# CPU.net
KiCad netlist of a schematic drawn in Altium Designer
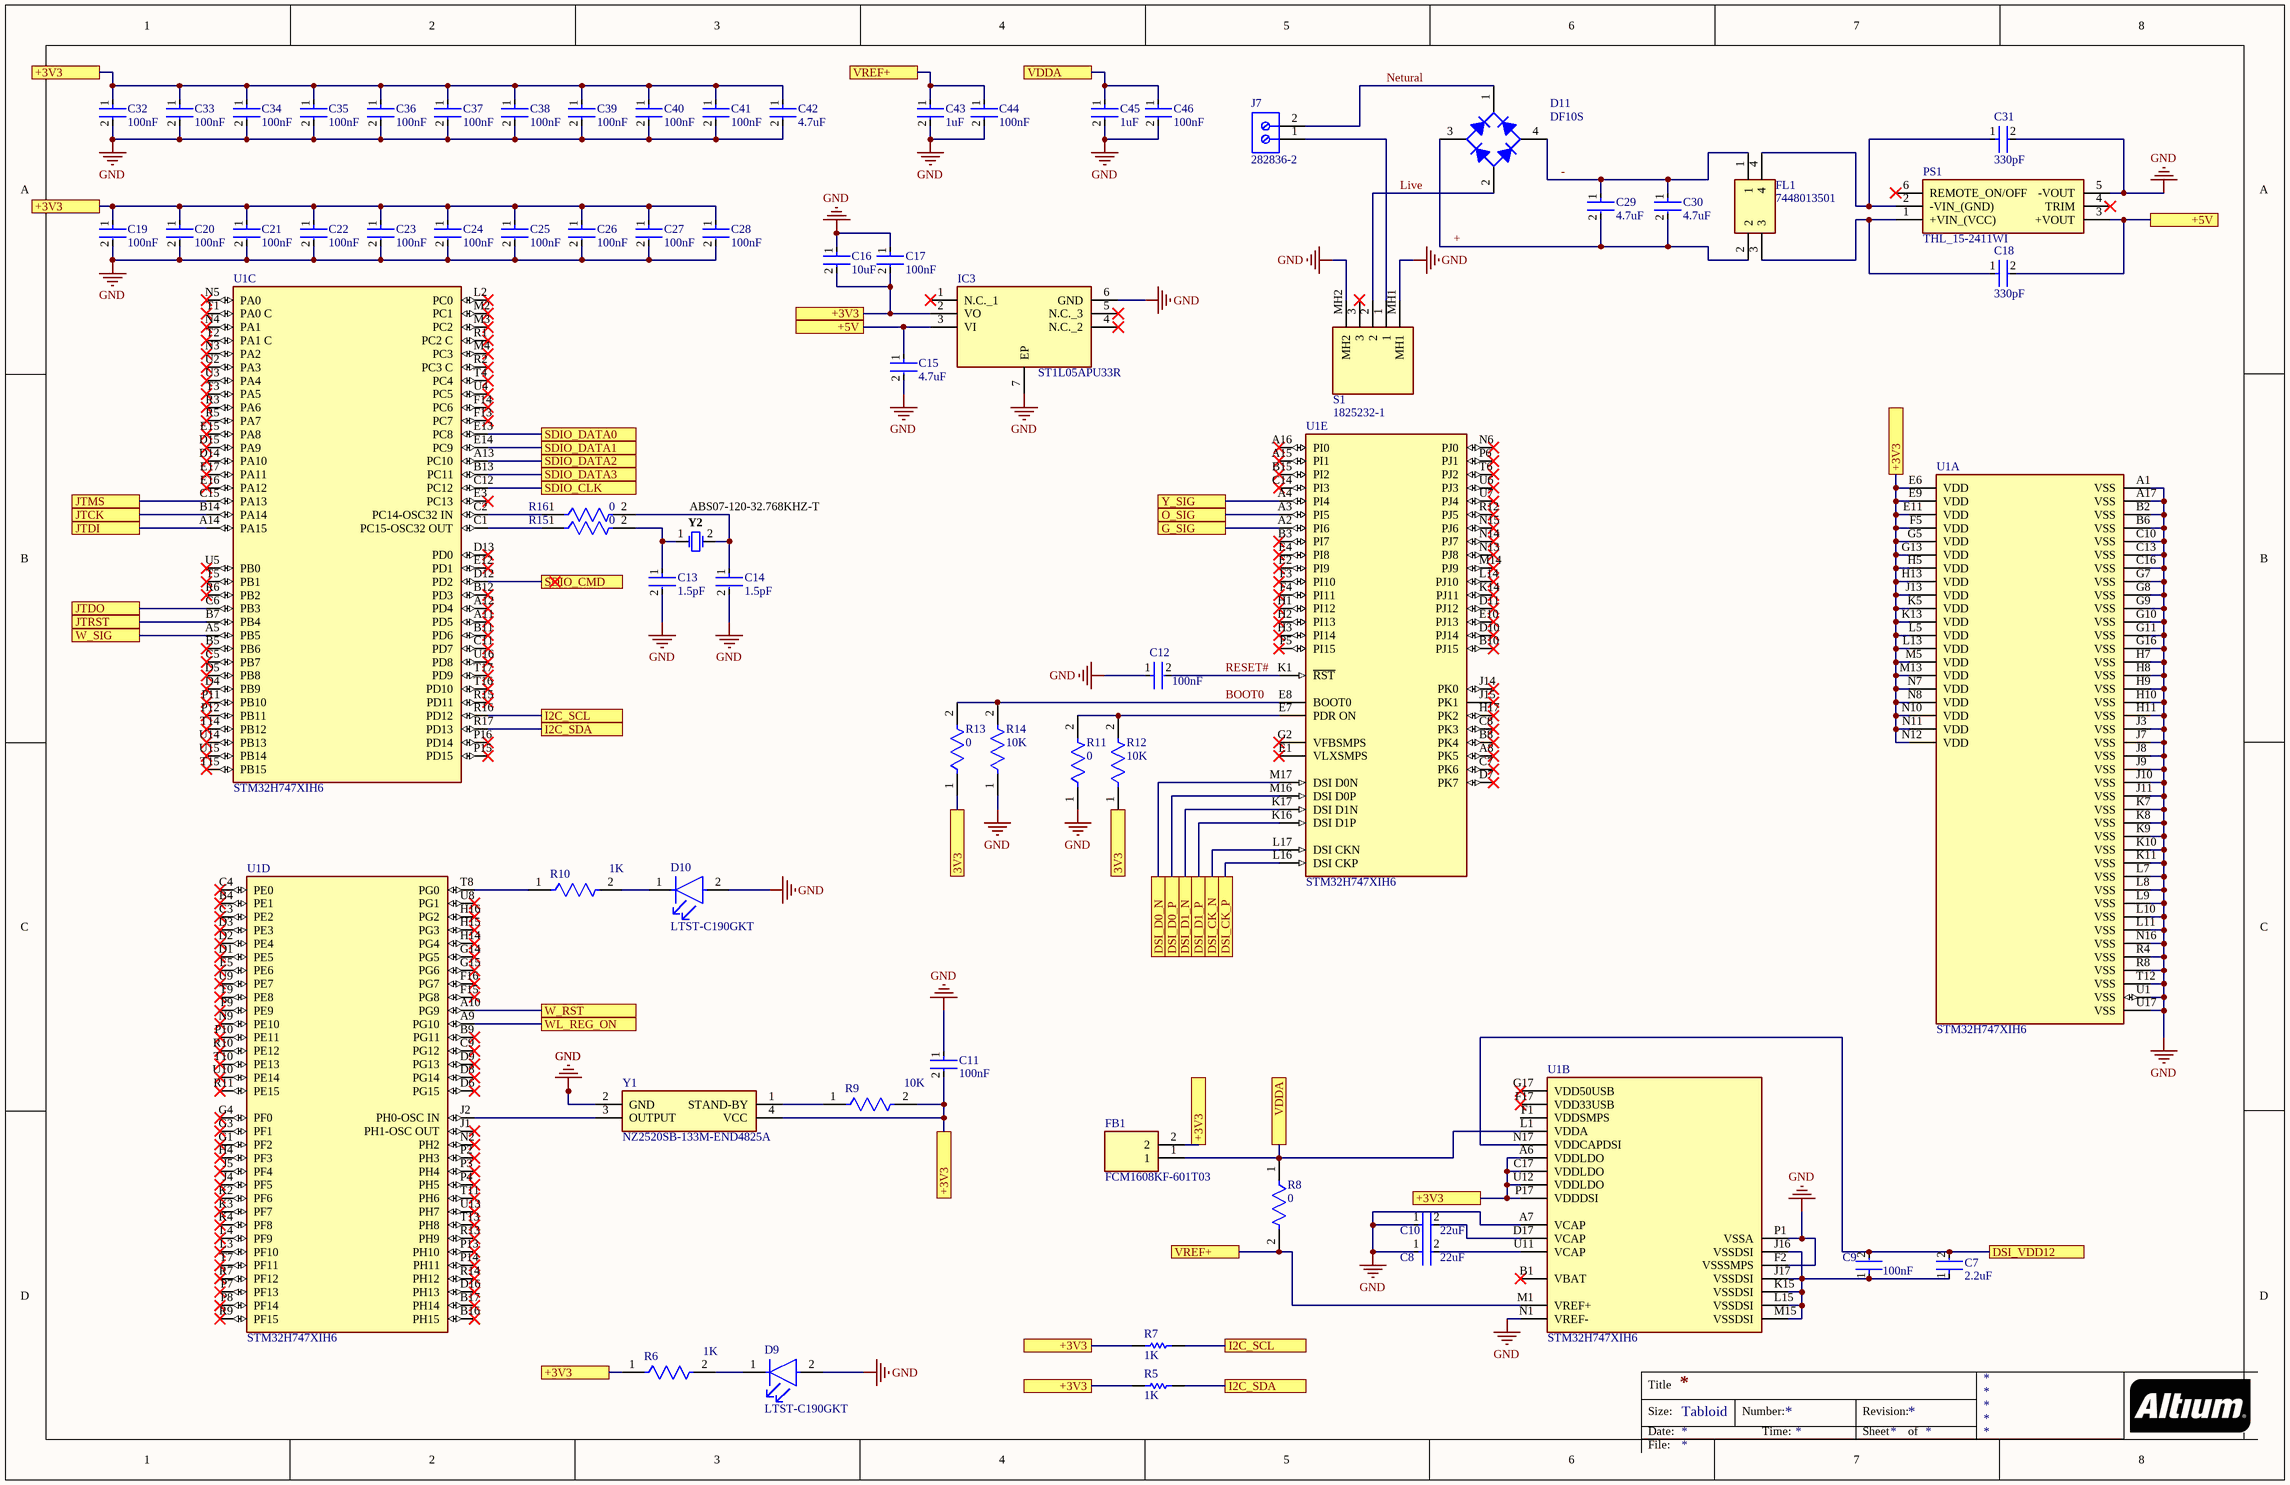
[diagram p0: CPU.SchDoc]

(export (version "E")
  (design (tool "Eeschema 10.0.6"))
  (components
    (comp (ref "C7")
      (value "2.2uF")
      (footprint "FP-GJM155-0_05-IPC_C")
      (description "Multi-Layer Ceramic Capacitor 1.5pF C0G  ±0.1pF 0402 Paper T/R")
      (fields (field (name "VOLTAGE") "50V"))
      (libsource (lib "Altium Content Vault") (part "02cd4be3c70576c341d710602a673aa"))
    )
    (comp (ref "C8")
      (value "22uF")
      (footprint "FP-GJM155-0_05-IPC_C")
      (description "Multi-Layer Ceramic Capacitor 1.5pF C0G  ±0.1pF 0402 Paper T/R")
      (fields (field (name "VOLTAGE") "50V"))
      (libsource (lib "Altium Content Vault") (part "02cd4be3c70576c341d710602a673aa"))
    )
    (comp (ref "C9")
      (value "100nF")
      (footprint "FP-GJM155-0_05-IPC_C")
      (description "Multi-Layer Ceramic Capacitor 1.5pF C0G  ±0.1pF 0402 Paper T/R")
      (fields (field (name "VOLTAGE") "50V"))
      (libsource (lib "Altium Content Vault") (part "02cd4be3c70576c341d710602a673aa"))
    )
    (comp (ref "C10")
      (value "22uF")
      (footprint "FP-GJM155-0_05-IPC_C")
      (description "Multi-Layer Ceramic Capacitor 1.5pF C0G  ±0.1pF 0402 Paper T/R")
      (fields (field (name "VOLTAGE") "50V"))
      (libsource (lib "Altium Content Vault") (part "02cd4be3c70576c341d710602a673aa"))
    )
    (comp (ref "C11")
      (value "100nF")
      (footprint "FP-GJM155-0_05-IPC_C")
      (description "Multi-Layer Ceramic Capacitor 1.5pF C0G  ±0.1pF 0402 Paper T/R")
      (fields (field (name "VOLTAGE") "50V"))
      (libsource (lib "Altium Content Vault") (part "02cd4be3c70576c341d710602a673aa"))
    )
    (comp (ref "C12")
      (value "100nF")
      (footprint "FP-GJM155-0_05-IPC_C")
      (description "Multi-Layer Ceramic Capacitor 1.5pF C0G  ±0.1pF 0402 Paper T/R")
      (fields (field (name "VOLTAGE") "50V"))
      (libsource (lib "Altium Content Vault") (part "02cd4be3c70576c341d710602a673aa"))
    )
    (comp (ref "C13")
      (value "1.5pF")
      (footprint "FP-GJM155-0_05-IPC_C")
      (description "Multi-Layer Ceramic Capacitor 1.5pF C0G  ±0.1pF 0402 Paper T/R")
      (fields (field (name "VOLTAGE") "50V"))
      (libsource (lib "Altium Content Vault") (part "02cd4be3c70576c341d710602a673aa"))
    )
    (comp (ref "C14")
      (value "1.5pF")
      (footprint "FP-GJM155-0_05-IPC_C")
      (description "Multi-Layer Ceramic Capacitor 1.5pF C0G  ±0.1pF 0402 Paper T/R")
      (fields (field (name "VOLTAGE") "50V"))
      (libsource (lib "Altium Content Vault") (part "02cd4be3c70576c341d710602a673aa"))
    )
    (comp (ref "C15")
      (value "4.7uF")
      (footprint "FP-GRM155-0_1-IPC_B")
      (description "Chip Multilayer Ceramic Capacitors for General Purpose, 0402, 4.7uF, X5R, 15%, 20%, 6.3V")
      (fields (field (name "VOLTAGE") "6.3V") (field (name "TOLERANCE") "20%"))
      (libsource (lib "Altium Content Vault") (part "11868f565c42a9108669ba33697ecf6"))
    )
    (comp (ref "C16")
      (value "10uF")
      (footprint "FP-GRM188-0_1-e0_2_0_55-IPC_A")
      (description "Chip Multilayer Ceramic Capacitors for General Purpose, 0603, 10uF, X5R, 15%, 20%, 6.3V")
      (fields (field (name "VOLTAGE") "6.3V") (field (name "TOLERANCE") "20%"))
      (libsource (lib "Altium Content Vault") (part "02cd4be3c70576c341d710602a673aa"))
    )
    (comp (ref "C17")
      (value "100nF")
      (footprint "FP-GRM033-0_03-MFG")
      (description "Chip Multilayer Ceramic Capacitors for General Purpose, 0201, 0.10uF, X5R, 15%, 10%, 6.3V")
      (fields (field (name "VOLTAGE") "6.3V") (field (name "TOLERANCE") "10%"))
      (libsource (lib "Altium Content Vault") (part "b4654b650e69147ec39a6b967a45e02"))
    )
    (comp (ref "C18")
      (value "330pF")
      (footprint "FP-GRM155-0_05-MFG")
      (description "Chip Multilayer Ceramic Capacitors for General Purpose, 0402, 330pF, C0G, 30ppm/°C, 5%, 50V")
      (fields (field (name "TOLERANCE") "5%") (field (name "VOLTAGE") "50V"))
      (libsource (lib "Altium Content Vault") (part "02cd4be3c70576c341d710602a673aa"))
    )
    (comp (ref "C19")
      (value "100nF")
      (footprint "FP-GRM033-0_03-MFG")
      (description "Chip Multilayer Ceramic Capacitors for General Purpose, 0201, 0.10uF, X5R, 15%, 10%, 6.3V")
      (fields (field (name "VOLTAGE") "6.3V") (field (name "TOLERANCE") "10%"))
      (libsource (lib "Altium Content Vault") (part "b4654b650e69147ec39a6b967a45e02"))
    )
    (comp (ref "C20")
      (value "100nF")
      (footprint "FP-GRM033-0_03-MFG")
      (description "Chip Multilayer Ceramic Capacitors for General Purpose, 0201, 0.10uF, X5R, 15%, 10%, 6.3V")
      (fields (field (name "VOLTAGE") "6.3V") (field (name "TOLERANCE") "10%"))
      (libsource (lib "Altium Content Vault") (part "b4654b650e69147ec39a6b967a45e02"))
    )
    (comp (ref "C21")
      (value "100nF")
      (footprint "FP-GRM033-0_03-MFG")
      (description "Chip Multilayer Ceramic Capacitors for General Purpose, 0201, 0.10uF, X5R, 15%, 10%, 6.3V")
      (fields (field (name "VOLTAGE") "6.3V") (field (name "TOLERANCE") "10%"))
      (libsource (lib "Altium Content Vault") (part "b4654b650e69147ec39a6b967a45e02"))
    )
    (comp (ref "C22")
      (value "100nF")
      (footprint "FP-GRM033-0_03-MFG")
      (description "Chip Multilayer Ceramic Capacitors for General Purpose, 0201, 0.10uF, X5R, 15%, 10%, 6.3V")
      (fields (field (name "VOLTAGE") "6.3V") (field (name "TOLERANCE") "10%"))
      (libsource (lib "Altium Content Vault") (part "b4654b650e69147ec39a6b967a45e02"))
    )
    (comp (ref "C23")
      (value "100nF")
      (footprint "FP-GRM033-0_03-MFG")
      (description "Chip Multilayer Ceramic Capacitors for General Purpose, 0201, 0.10uF, X5R, 15%, 10%, 6.3V")
      (fields (field (name "VOLTAGE") "6.3V") (field (name "TOLERANCE") "10%"))
      (libsource (lib "Altium Content Vault") (part "b4654b650e69147ec39a6b967a45e02"))
    )
    (comp (ref "C24")
      (value "100nF")
      (footprint "FP-GRM033-0_03-MFG")
      (description "Chip Multilayer Ceramic Capacitors for General Purpose, 0201, 0.10uF, X5R, 15%, 10%, 6.3V")
      (fields (field (name "VOLTAGE") "6.3V") (field (name "TOLERANCE") "10%"))
      (libsource (lib "Altium Content Vault") (part "b4654b650e69147ec39a6b967a45e02"))
    )
    (comp (ref "C25")
      (value "100nF")
      (footprint "FP-GRM033-0_03-MFG")
      (description "Chip Multilayer Ceramic Capacitors for General Purpose, 0201, 0.10uF, X5R, 15%, 10%, 6.3V")
      (fields (field (name "VOLTAGE") "6.3V") (field (name "TOLERANCE") "10%"))
      (libsource (lib "Altium Content Vault") (part "b4654b650e69147ec39a6b967a45e02"))
    )
    (comp (ref "C26")
      (value "100nF")
      (footprint "FP-GRM033-0_03-MFG")
      (description "Chip Multilayer Ceramic Capacitors for General Purpose, 0201, 0.10uF, X5R, 15%, 10%, 6.3V")
      (fields (field (name "VOLTAGE") "6.3V") (field (name "TOLERANCE") "10%"))
      (libsource (lib "Altium Content Vault") (part "b4654b650e69147ec39a6b967a45e02"))
    )
    (comp (ref "C27")
      (value "100nF")
      (footprint "FP-GRM033-0_03-MFG")
      (description "Chip Multilayer Ceramic Capacitors for General Purpose, 0201, 0.10uF, X5R, 15%, 10%, 6.3V")
      (fields (field (name "VOLTAGE") "6.3V") (field (name "TOLERANCE") "10%"))
      (libsource (lib "Altium Content Vault") (part "b4654b650e69147ec39a6b967a45e02"))
    )
    (comp (ref "C28")
      (value "100nF")
      (footprint "FP-GRM033-0_03-MFG")
      (description "Chip Multilayer Ceramic Capacitors for General Purpose, 0201, 0.10uF, X5R, 15%, 10%, 6.3V")
      (fields (field (name "VOLTAGE") "6.3V") (field (name "TOLERANCE") "10%"))
      (libsource (lib "Altium Content Vault") (part "b4654b650e69147ec39a6b967a45e02"))
    )
    (comp (ref "C29")
      (value "4.7uF")
      (footprint "FP-GRM155-0_1-IPC_B")
      (description "Chip Multilayer Ceramic Capacitors for General Purpose, 0402, 4.7uF, X5R, 15%, 20%, 6.3V")
      (fields (field (name "VOLTAGE") "6.3V") (field (name "TOLERANCE") "20%"))
      (libsource (lib "Altium Content Vault") (part "11868f565c42a9108669ba33697ecf6"))
    )
    (comp (ref "C30")
      (value "4.7uF")
      (footprint "FP-GRM155-0_1-IPC_B")
      (description "Chip Multilayer Ceramic Capacitors for General Purpose, 0402, 4.7uF, X5R, 15%, 20%, 6.3V")
      (fields (field (name "VOLTAGE") "6.3V") (field (name "TOLERANCE") "20%"))
      (libsource (lib "Altium Content Vault") (part "11868f565c42a9108669ba33697ecf6"))
    )
    (comp (ref "C31")
      (value "330pF")
      (footprint "FP-GRM155-0_05-MFG")
      (description "Chip Multilayer Ceramic Capacitors for General Purpose, 0402, 330pF, C0G, 30ppm/°C, 5%, 50V")
      (fields (field (name "TOLERANCE") "5%") (field (name "VOLTAGE") "50V"))
      (libsource (lib "Altium Content Vault") (part "02cd4be3c70576c341d710602a673aa"))
    )
    (comp (ref "C32")
      (value "100nF")
      (footprint "FP-GRM033-0_03-MFG")
      (description "Chip Multilayer Ceramic Capacitors for General Purpose, 0201, 0.10uF, X5R, 15%, 10%, 6.3V")
      (fields (field (name "VOLTAGE") "6.3V") (field (name "TOLERANCE") "10%"))
      (libsource (lib "Altium Content Vault") (part "b4654b650e69147ec39a6b967a45e02"))
    )
    (comp (ref "C33")
      (value "100nF")
      (footprint "FP-GRM033-0_03-MFG")
      (description "Chip Multilayer Ceramic Capacitors for General Purpose, 0201, 0.10uF, X5R, 15%, 10%, 6.3V")
      (fields (field (name "VOLTAGE") "6.3V") (field (name "TOLERANCE") "10%"))
      (libsource (lib "Altium Content Vault") (part "b4654b650e69147ec39a6b967a45e02"))
    )
    (comp (ref "C34")
      (value "100nF")
      (footprint "FP-GRM033-0_03-MFG")
      (description "Chip Multilayer Ceramic Capacitors for General Purpose, 0201, 0.10uF, X5R, 15%, 10%, 6.3V")
      (fields (field (name "VOLTAGE") "6.3V") (field (name "TOLERANCE") "10%"))
      (libsource (lib "Altium Content Vault") (part "b4654b650e69147ec39a6b967a45e02"))
    )
    (comp (ref "C35")
      (value "100nF")
      (footprint "FP-GRM033-0_03-MFG")
      (description "Chip Multilayer Ceramic Capacitors for General Purpose, 0201, 0.10uF, X5R, 15%, 10%, 6.3V")
      (fields (field (name "VOLTAGE") "6.3V") (field (name "TOLERANCE") "10%"))
      (libsource (lib "Altium Content Vault") (part "b4654b650e69147ec39a6b967a45e02"))
    )
    (comp (ref "C36")
      (value "100nF")
      (footprint "FP-GRM033-0_03-MFG")
      (description "Chip Multilayer Ceramic Capacitors for General Purpose, 0201, 0.10uF, X5R, 15%, 10%, 6.3V")
      (fields (field (name "VOLTAGE") "6.3V") (field (name "TOLERANCE") "10%"))
      (libsource (lib "Altium Content Vault") (part "b4654b650e69147ec39a6b967a45e02"))
    )
    (comp (ref "C37")
      (value "100nF")
      (footprint "FP-GRM033-0_03-MFG")
      (description "Chip Multilayer Ceramic Capacitors for General Purpose, 0201, 0.10uF, X5R, 15%, 10%, 6.3V")
      (fields (field (name "VOLTAGE") "6.3V") (field (name "TOLERANCE") "10%"))
      (libsource (lib "Altium Content Vault") (part "b4654b650e69147ec39a6b967a45e02"))
    )
    (comp (ref "C38")
      (value "100nF")
      (footprint "FP-GRM033-0_03-MFG")
      (description "Chip Multilayer Ceramic Capacitors for General Purpose, 0201, 0.10uF, X5R, 15%, 10%, 6.3V")
      (fields (field (name "VOLTAGE") "6.3V") (field (name "TOLERANCE") "10%"))
      (libsource (lib "Altium Content Vault") (part "b4654b650e69147ec39a6b967a45e02"))
    )
    (comp (ref "C39")
      (value "100nF")
      (footprint "FP-GRM033-0_03-MFG")
      (description "Chip Multilayer Ceramic Capacitors for General Purpose, 0201, 0.10uF, X5R, 15%, 10%, 6.3V")
      (fields (field (name "VOLTAGE") "6.3V") (field (name "TOLERANCE") "10%"))
      (libsource (lib "Altium Content Vault") (part "b4654b650e69147ec39a6b967a45e02"))
    )
    (comp (ref "C40")
      (value "100nF")
      (footprint "FP-GRM033-0_03-MFG")
      (description "Chip Multilayer Ceramic Capacitors for General Purpose, 0201, 0.10uF, X5R, 15%, 10%, 6.3V")
      (fields (field (name "VOLTAGE") "6.3V") (field (name "TOLERANCE") "10%"))
      (libsource (lib "Altium Content Vault") (part "b4654b650e69147ec39a6b967a45e02"))
    )
    (comp (ref "C41")
      (value "100nF")
      (footprint "FP-GRM033-0_03-MFG")
      (description "Chip Multilayer Ceramic Capacitors for General Purpose, 0201, 0.10uF, X5R, 15%, 10%, 6.3V")
      (fields (field (name "VOLTAGE") "6.3V") (field (name "TOLERANCE") "10%"))
      (libsource (lib "Altium Content Vault") (part "b4654b650e69147ec39a6b967a45e02"))
    )
    (comp (ref "C42")
      (value "4.7uF")
      (footprint "FP-GRM155-0_1-IPC_B")
      (description "Chip Multilayer Ceramic Capacitors for General Purpose, 0402, 4.7uF, X5R, 15%, 20%, 6.3V")
      (fields (field (name "VOLTAGE") "6.3V") (field (name "TOLERANCE") "20%"))
      (libsource (lib "Altium Content Vault") (part "11868f565c42a9108669ba33697ecf6"))
    )
    (comp (ref "C43")
      (value "1uF")
      (footprint "FP-GRM15-0_1-MFG")
      (description "CAP CER 1UF 10V X5R 0402")
      (fields
        (field (name "OCTOPART") "https://octopart.com/grm155r61a105ke15d-murata-197442")
        (field (name "MANUFACTURER PART NUMBER") "GRM155R61A105KE15D")
      )
      (libsource (lib "Altium Content Vault") (part "02cd4be3c70576c341d710602a673aa"))
    )
    (comp (ref "C44")
      (value "100nF")
      (footprint "FP-GRM033-0_03-MFG")
      (description "Chip Multilayer Ceramic Capacitors for General Purpose, 0201, 0.10uF, X5R, 15%, 10%, 6.3V")
      (fields (field (name "VOLTAGE") "6.3V") (field (name "TOLERANCE") "10%"))
      (libsource (lib "Altium Content Vault") (part "b4654b650e69147ec39a6b967a45e02"))
    )
    (comp (ref "C45")
      (value "1uF")
      (footprint "FP-GRM15-0_1-MFG")
      (description "CAP CER 1UF 10V X5R 0402")
      (fields
        (field (name "OCTOPART") "https://octopart.com/grm155r61a105ke15d-murata-197442")
        (field (name "MANUFACTURER PART NUMBER") "GRM155R61A105KE15D")
      )
      (libsource (lib "Altium Content Vault") (part "02cd4be3c70576c341d710602a673aa"))
    )
    (comp (ref "C46")
      (value "100nF")
      (footprint "FP-GRM033-0_03-MFG")
      (description "Chip Multilayer Ceramic Capacitors for General Purpose, 0201, 0.10uF, X5R, 15%, 10%, 6.3V")
      (fields (field (name "VOLTAGE") "6.3V") (field (name "TOLERANCE") "10%"))
      (libsource (lib "Altium Content Vault") (part "b4654b650e69147ec39a6b967a45e02"))
    )
    (comp (ref "D9")
      (value "LTST-C190GKT")
      (footprint "FP-LTST-C190GKT-MFG")
      (description "LED GREEN CLEAR CHIP SMD")
      (fields (field (name "VOLTAGE") "2V"))
      (libsource (lib "Altium Content Vault") (part "8706943c75ba83719d021d2fdc84c58"))
    )
    (comp (ref "D10")
      (value "LTST-C190GKT")
      (footprint "FP-LTST-C190GKT-MFG")
      (description "LED GREEN CLEAR CHIP SMD")
      (fields (field (name "VOLTAGE") "2V"))
      (libsource (lib "Altium Content Vault") (part "8706943c75ba83719d021d2fdc84c58"))
    )
    (comp (ref "D11")
      (value "DF10S")
      (footprint "FAIR-SDIP-4_V")
      (description "Bridge Rectifier, 1.5 A, 1000 V, 4-Pin SDIP, RoHS, Tape and Reel")
      (fields (field (name "MANUFACTURER") "FairchildSemiconductor"))
      (libsource (lib "Altium Content Vault") (part "D-KACC-4"))
    )
    (comp (ref "FB1")
      (value "FCM1608KF-601T03")
      (footprint "SamacSys:BEADC1608X95N")
      (description "Ferrite Bead")
      (libsource (lib "*") (part "FCM1608KF-601T03"))
    )
    (comp (ref "FL1")
      (value "7448013501")
      (footprint "SamacSys:7448013501")
      (description "Filter")
      (fields (field (name "MOUSER PART NUMBER") "710-7448013501"))
      (libsource (lib "*") (part "7448013501"))
    )
    (comp (ref "IC3")
      (value "ST1L05APU33R")
      (footprint "SamacSys:SON95P300X300X100-7N-D")
      (description "Integrated Circuit")
      (fields (field (name "MOUSER PART NUMBER") "511-ST1L05APU33R"))
      (libsource (lib "*") (part "ST1L05APU33R"))
    )
    (comp (ref "J7")
      (value "282836-2")
      (footprint "TECO-282836-2_V")
      (description "Female Header, Pitch 5 mm, 1 x 2 Position, Height 10 mm, Tail Length 3.5 mm, Rohs, Bulk")
      (fields (field (name "VOLTAGE") "300V") (field (name "MANUFACTURER") "TE Connectivity"))
      (libsource (lib "Altium Content Vault") (part "CN-1P-F-TB2"))
    )
    (comp (ref "PS1")
      (value "THL_15-2411WI")
      (footprint "SamacSys:THL152411WI")
      (description "Power Supply")
      (fields
        (field (name "MANUFACTURER_PART_NUMBER") "THL 15-2411WI")
        (field (name "MOUSER PART NUMBER") "495-THL15-2411WI")
      )
      (libsource (lib "*") (part "THL_15-2411WI"))
    )
    (comp (ref "R5")
      (value "1K")
      (footprint "RESC1608X55X30LL20T20")
      (fields (field (name "MANUFACTURER") "Panasonic") (field (name "PART NUMBER") "ERA3AEB102V"))
      (libsource (lib "Altium Content Vault") (part "RES"))
    )
    (comp (ref "R6")
      (value "1K")
      (footprint "FP-CRCW0402-e3-MFG")
      (description "RES Thick Film, 1kΩ, 1%, 0.063W, 100ppm/°C, 0402")
      (fields (field (name "TOLERANCE") "1%"))
      (libsource (lib "Altium Content Vault") (part "1029c3af85768c4190bb7ad29bc67b5"))
    )
    (comp (ref "R7")
      (value "1K")
      (footprint "RESC1608X55X30LL20T20")
      (fields (field (name "MANUFACTURER") "Panasonic") (field (name "PART NUMBER") "ERA3AEB102V"))
      (libsource (lib "Altium Content Vault") (part "RES"))
    )
    (comp (ref "R8")
      (value "0")
      (footprint "FP-CRCW0402-e3-IPC_C")
      (description "RES Thick Film, 0Ω, 0.063W, 0402")
      (fields (field (name "TOLERANCE") "5%"))
      (libsource (lib "Altium Content Vault") (part "1029c3af85768c4190bb7ad29bc67b5"))
    )
    (comp (ref "R9")
      (value "10K")
      (footprint "FP-CRCW0402-e3-MFG")
      (description "RES Thick Film, 1kΩ, 1%, 0.063W, 100ppm/°C, 0402")
      (fields (field (name "TOLERANCE") "1%"))
      (libsource (lib "Altium Content Vault") (part "1029c3af85768c4190bb7ad29bc67b5"))
    )
    (comp (ref "R10")
      (value "1K")
      (footprint "FP-CRCW0402-e3-MFG")
      (description "RES Thick Film, 1kΩ, 1%, 0.063W, 100ppm/°C, 0402")
      (fields (field (name "TOLERANCE") "1%"))
      (libsource (lib "Altium Content Vault") (part "1029c3af85768c4190bb7ad29bc67b5"))
    )
    (comp (ref "R11")
      (value "0")
      (footprint "FP-CRCW0402-e3-IPC_C")
      (description "RES Thick Film, 0Ω, 0.063W, 0402")
      (fields (field (name "TOLERANCE") "5%"))
      (libsource (lib "Altium Content Vault") (part "1029c3af85768c4190bb7ad29bc67b5"))
    )
    (comp (ref "R12")
      (value "10K")
      (footprint "FP-CRCW0402-e3-IPC_C")
      (description "RES Thick Film, 0Ω, 0.063W, 0402")
      (fields (field (name "TOLERANCE") "5%"))
      (libsource (lib "Altium Content Vault") (part "1029c3af85768c4190bb7ad29bc67b5"))
    )
    (comp (ref "R13")
      (value "0")
      (footprint "FP-CRCW0402-e3-IPC_C")
      (description "RES Thick Film, 0Ω, 0.063W, 0402")
      (fields (field (name "TOLERANCE") "5%"))
      (libsource (lib "Altium Content Vault") (part "1029c3af85768c4190bb7ad29bc67b5"))
    )
    (comp (ref "R14")
      (value "10K")
      (footprint "FP-CRCW0402-e3-IPC_C")
      (description "RES Thick Film, 0Ω, 0.063W, 0402")
      (fields (field (name "TOLERANCE") "5%"))
      (libsource (lib "Altium Content Vault") (part "1029c3af85768c4190bb7ad29bc67b5"))
    )
    (comp (ref "R15")
      (value "0")
      (footprint "FP-CRCW0402-e3-IPC_C")
      (description "RES Thick Film, 0Ω, 0.063W, 0402")
      (fields (field (name "TOLERANCE") "5%"))
      (libsource (lib "Altium Content Vault") (part "1029c3af85768c4190bb7ad29bc67b5"))
    )
    (comp (ref "R16")
      (value "0")
      (footprint "FP-CRCW0402-e3-IPC_C")
      (description "RES Thick Film, 0Ω, 0.063W, 0402")
      (fields (field (name "TOLERANCE") "5%"))
      (libsource (lib "Altium Content Vault") (part "1029c3af85768c4190bb7ad29bc67b5"))
    )
    (comp (ref "S1")
      (value "1825232-1")
      (footprint "SamacSys:18252321")
      (description "Switch")
      (fields (field (name "MOUSER PART NUMBER") "655-1825232-1"))
      (libsource (lib "*") (part "1825232-1"))
    )
    (comp (ref "U1")
      (value "STM32H747XIH6")
      (footprint "FP-TFBGA240+25-A07U-MFG")
      (description "HIGH-PERFORMANCE AND DSP WITH DP")
      (fields
        (field (name "MANUFACTURER") "STMicroelectronics")
        (field (name "OCTOPART") "https://octopart.com/stm32h747xih6-stmicroelectronics-100293943")
      )
      (libsource (lib "Altium Content Vault") (part "41f839bdfd00d9510c8672f0f410bfb"))
    )
    (comp (ref "Y1")
      (value "NZ2520SB-133M-END4825A")
      (footprint "SamacSys:NZ2520SD")
      (description "Crystal or Oscillator")
      (fields (field (name "MOUSER PART NUMBER") "344-NZ2520SB1334825A"))
      (libsource (lib "*") (part "NZ2520SB-133M-END4825A"))
    )
    (comp (ref "Y2")
      (value "ABS07-120-32.768KHZ-T")
      (footprint "ABRA-ABS07_A_V")
      (description "Tuning Fork Crystal, 32.768 KHz, +/- 20 ppm, -40 to 85 degC, 2-Pin SMD, RoHS, Tape and Reel")
      (fields (field (name "MANUFACTURER") "Abracon") (field (name "TOLERANCE") "20ppm"))
      (libsource (lib "Altium Content Vault") (part "XTAL-1-2-2"))
    )
  )
  (nets
    (net (code "1") (name "/+") (class "Default")
      (node (ref "C29") (pin "2") (pinfunction "2_2") (pintype "passive"))
      (node (ref "C30") (pin "2") (pinfunction "2_2") (pintype "passive"))
      (node (ref "D11") (pin "3") (pinfunction "C_3") (pintype "passive"))
      (node (ref "FL1") (pin "2") (pinfunction "2_2") (pintype "passive"))
    )
    (net (code "2") (name "/+3V3") (class "Default")
      (node (ref "C11") (pin "2") (pinfunction "2_2") (pintype "passive"))
      (node (ref "C16") (pin "2") (pinfunction "2_2") (pintype "passive"))
      (node (ref "C17") (pin "2") (pinfunction "2_2") (pintype "passive"))
      (node (ref "C19") (pin "1") (pinfunction "1_1") (pintype "passive"))
      (node (ref "C20") (pin "1") (pinfunction "1_1") (pintype "passive"))
      (node (ref "C21") (pin "1") (pinfunction "1_1") (pintype "passive"))
      (node (ref "C22") (pin "1") (pinfunction "1_1") (pintype "passive"))
      (node (ref "C23") (pin "1") (pinfunction "1_1") (pintype "passive"))
      (node (ref "C24") (pin "1") (pinfunction "1_1") (pintype "passive"))
      (node (ref "C25") (pin "1") (pinfunction "1_1") (pintype "passive"))
      (node (ref "C26") (pin "1") (pinfunction "1_1") (pintype "passive"))
      (node (ref "C27") (pin "1") (pinfunction "1_1") (pintype "passive"))
      (node (ref "C28") (pin "1") (pinfunction "1_1") (pintype "passive"))
      (node (ref "C32") (pin "1") (pinfunction "1_1") (pintype "passive"))
      (node (ref "C33") (pin "1") (pinfunction "1_1") (pintype "passive"))
      (node (ref "C34") (pin "1") (pinfunction "1_1") (pintype "passive"))
      (node (ref "C35") (pin "1") (pinfunction "1_1") (pintype "passive"))
      (node (ref "C36") (pin "1") (pinfunction "1_1") (pintype "passive"))
      (node (ref "C37") (pin "1") (pinfunction "1_1") (pintype "passive"))
      (node (ref "C38") (pin "1") (pinfunction "1_1") (pintype "passive"))
      (node (ref "C39") (pin "1") (pinfunction "1_1") (pintype "passive"))
      (node (ref "C40") (pin "1") (pinfunction "1_1") (pintype "passive"))
      (node (ref "C41") (pin "1") (pinfunction "1_1") (pintype "passive"))
      (node (ref "C42") (pin "1") (pinfunction "1_1") (pintype "passive"))
      (node (ref "FB1") (pin "2") (pinfunction "2_2") (pintype "passive"))
      (node (ref "IC3") (pin "2") (pinfunction "VO_2") (pintype "passive"))
      (node (ref "R5") (pin "1") (pinfunction "1_1") (pintype "passive"))
      (node (ref "R6") (pin "1") (pinfunction "1_1") (pintype "passive"))
      (node (ref "R7") (pin "1") (pinfunction "1_1") (pintype "passive"))
      (node (ref "R9") (pin "2") (pinfunction "2_2") (pintype "passive"))
      (node (ref "U1") (pin "A6") (pinfunction "VDDLDO_A6") (pintype "power_in"))
      (node (ref "U1") (pin "C17") (pinfunction "VDDLDO_C17") (pintype "power_in"))
      (node (ref "U1") (pin "E11") (pinfunction "VDD_E11") (pintype "power_in"))
      (node (ref "U1") (pin "E6") (pinfunction "VDD_E6") (pintype "power_in"))
      (node (ref "U1") (pin "E9") (pinfunction "VDD_E9") (pintype "power_in"))
      (node (ref "U1") (pin "F5") (pinfunction "VDD_F5") (pintype "power_in"))
      (node (ref "U1") (pin "G13") (pinfunction "VDD_G13") (pintype "power_in"))
      (node (ref "U1") (pin "G5") (pinfunction "VDD_G5") (pintype "power_in"))
      (node (ref "U1") (pin "H13") (pinfunction "VDD_H13") (pintype "power_in"))
      (node (ref "U1") (pin "H5") (pinfunction "VDD_H5") (pintype "power_in"))
      (node (ref "U1") (pin "J13") (pinfunction "VDD_J13") (pintype "power_in"))
      (node (ref "U1") (pin "K13") (pinfunction "VDD_K13") (pintype "power_in"))
      (node (ref "U1") (pin "K5") (pinfunction "VDD_K5") (pintype "power_in"))
      (node (ref "U1") (pin "L13") (pinfunction "VDD_L13") (pintype "power_in"))
      (node (ref "U1") (pin "L5") (pinfunction "VDD_L5") (pintype "power_in"))
      (node (ref "U1") (pin "M13") (pinfunction "VDD_M13") (pintype "power_in"))
      (node (ref "U1") (pin "M5") (pinfunction "VDD_M5") (pintype "power_in"))
      (node (ref "U1") (pin "N10") (pinfunction "VDD_N10") (pintype "power_in"))
      (node (ref "U1") (pin "N11") (pinfunction "VDD_N11") (pintype "power_in"))
      (node (ref "U1") (pin "N12") (pinfunction "VDD_N12") (pintype "power_in"))
      (node (ref "U1") (pin "N7") (pinfunction "VDD_N7") (pintype "power_in"))
      (node (ref "U1") (pin "N8") (pinfunction "VDD_N8") (pintype "power_in"))
      (node (ref "U1") (pin "P17") (pinfunction "VDDDSI_P17") (pintype "power_in"))
      (node (ref "U1") (pin "U12") (pinfunction "VDDLDO_U12") (pintype "power_in"))
      (node (ref "Y1") (pin "4") (pinfunction "VCC_4") (pintype "passive"))
    )
    (net (code "3") (name "/+5V") (class "Default")
      (node (ref "C15") (pin "1") (pinfunction "1_1") (pintype "passive"))
      (node (ref "C18") (pin "2") (pinfunction "2_2") (pintype "passive"))
      (node (ref "IC3") (pin "3") (pinfunction "VI_3") (pintype "passive"))
      (node (ref "PS1") (pin "3") (pinfunction "+VOUT_3") (pintype "passive"))
    )
    (net (code "4") (name "/-") (class "Default")
      (node (ref "C29") (pin "1") (pinfunction "1_1") (pintype "passive"))
      (node (ref "C30") (pin "1") (pinfunction "1_1") (pintype "passive"))
      (node (ref "D11") (pin "4") (pinfunction "C_4") (pintype "passive"))
      (node (ref "FL1") (pin "1") (pinfunction "1_1") (pintype "passive"))
    )
    (net (code "5") (name "/3V3") (class "Default")
      (node (ref "R12") (pin "1") (pinfunction "1_1") (pintype "passive"))
      (node (ref "R13") (pin "1") (pinfunction "1_1") (pintype "passive"))
    )
    (net (code "6") (name "/BOOT0") (class "Default")
      (node (ref "R13") (pin "2") (pinfunction "2_2") (pintype "passive"))
      (node (ref "R14") (pin "2") (pinfunction "2_2") (pintype "passive"))
      (node (ref "U1") (pin "E8") (pinfunction "BOOT0_E8") (pintype "passive"))
    )
    (net (code "7") (name "/DSI_CK_N") (class "Default")
      (node (ref "U1") (pin "L17") (pinfunction "DSI_CKN_L17") (pintype "input"))
    )
    (net (code "8") (name "/DSI_CK_P") (class "Default")
      (node (ref "U1") (pin "L16") (pinfunction "DSI_CKP_L16") (pintype "input"))
    )
    (net (code "9") (name "/DSI_D0_N") (class "Default")
      (node (ref "U1") (pin "M17") (pinfunction "DSI_D0N_M17") (pintype "input"))
    )
    (net (code "10") (name "/DSI_D0_P") (class "Default")
      (node (ref "U1") (pin "M16") (pinfunction "DSI_D0P_M16") (pintype "input"))
    )
    (net (code "11") (name "/DSI_D1_N") (class "Default")
      (node (ref "U1") (pin "K17") (pinfunction "DSI_D1N_K17") (pintype "input"))
    )
    (net (code "12") (name "/DSI_D1_P") (class "Default")
      (node (ref "U1") (pin "K16") (pinfunction "DSI_D1P_K16") (pintype "input"))
    )
    (net (code "13") (name "/DSI_VDD12") (class "Default")
      (node (ref "C7") (pin "2") (pinfunction "2_2") (pintype "passive"))
      (node (ref "C9") (pin "2") (pinfunction "2_2") (pintype "passive"))
      (node (ref "U1") (pin "N17") (pinfunction "VDDCAPDSI_N17") (pintype "power_in"))
    )
    (net (code "14") (name "/G_SIG") (class "Default")
      (node (ref "U1") (pin "A2") (pinfunction "PI6_A2") (pintype "bidirectional"))
    )
    (net (code "15") (name "/I2C_SCL") (class "Default")
      (node (ref "R7") (pin "2") (pinfunction "2_2") (pintype "passive"))
      (node (ref "U1") (pin "R16") (pinfunction "PD12_R16") (pintype "bidirectional"))
    )
    (net (code "16") (name "/I2C_SDA") (class "Default")
      (node (ref "R5") (pin "2") (pinfunction "2_2") (pintype "passive"))
      (node (ref "U1") (pin "R17") (pinfunction "PD13_R17") (pintype "bidirectional"))
    )
    (net (code "17") (name "/JTCK") (class "Default")
      (node (ref "U1") (pin "B14") (pinfunction "PA14_B14") (pintype "bidirectional"))
    )
    (net (code "18") (name "/JTDI") (class "Default")
      (node (ref "U1") (pin "A14") (pinfunction "PA15_A14") (pintype "bidirectional"))
    )
    (net (code "19") (name "/JTDO") (class "Default")
      (node (ref "U1") (pin "C6") (pinfunction "PB3_C6") (pintype "bidirectional"))
    )
    (net (code "20") (name "/JTMS") (class "Default")
      (node (ref "U1") (pin "C15") (pinfunction "PA13_C15") (pintype "bidirectional"))
    )
    (net (code "21") (name "/JTRST") (class "Default")
      (node (ref "U1") (pin "B7") (pinfunction "PB4_B7") (pintype "bidirectional"))
    )
    (net (code "22") (name "/Live") (class "Default")
      (node (ref "D11") (pin "2") (pinfunction "A_2") (pintype "passive"))
      (node (ref "S1") (pin "2") (pinfunction "2_2") (pintype "passive"))
    )
    (net (code "23") (name "/Netural") (class "Default")
      (node (ref "D11") (pin "1") (pinfunction "K_1") (pintype "passive"))
      (node (ref "J7") (pin "2") (pinfunction "2_2") (pintype "passive"))
    )
    (net (code "24") (name "/O_SIG") (class "Default")
      (node (ref "U1") (pin "A3") (pinfunction "PI5_A3") (pintype "bidirectional"))
    )
    (net (code "25") (name "/RESET#") (class "Default")
      (node (ref "C12") (pin "2") (pinfunction "2_2") (pintype "passive"))
      (node (ref "U1") (pin "K1") (pinfunction "~{RST}_K1") (pintype "input"))
    )
    (net (code "26") (name "/SDIO_CLK") (class "Default")
      (node (ref "U1") (pin "C12") (pinfunction "PC12_C12") (pintype "bidirectional"))
    )
    (net (code "27") (name "/SDIO_CMD") (class "Default")
      (node (ref "U1") (pin "D12") (pinfunction "PD2_D12") (pintype "bidirectional"))
    )
    (net (code "28") (name "/SDIO_DATA0") (class "Default")
      (node (ref "U1") (pin "E13") (pinfunction "PC8_E13") (pintype "bidirectional"))
    )
    (net (code "29") (name "/SDIO_DATA1") (class "Default")
      (node (ref "U1") (pin "E14") (pinfunction "PC9_E14") (pintype "bidirectional"))
    )
    (net (code "30") (name "/SDIO_DATA2") (class "Default")
      (node (ref "U1") (pin "A13") (pinfunction "PC10_A13") (pintype "bidirectional"))
    )
    (net (code "31") (name "/SDIO_DATA3") (class "Default")
      (node (ref "U1") (pin "B13") (pinfunction "PC11_B13") (pintype "bidirectional"))
    )
    (net (code "32") (name "/VDDA") (class "Default")
      (node (ref "C45") (pin "1") (pinfunction "1_1") (pintype "passive"))
      (node (ref "C46") (pin "1") (pinfunction "1_1") (pintype "passive"))
      (node (ref "FB1") (pin "1") (pinfunction "1_1") (pintype "passive"))
      (node (ref "R8") (pin "1") (pinfunction "1_1") (pintype "passive"))
      (node (ref "U1") (pin "L1") (pinfunction "VDDA_L1") (pintype "power_in"))
    )
    (net (code "33") (name "/VREF+") (class "Default")
      (node (ref "C43") (pin "1") (pinfunction "1_1") (pintype "passive"))
      (node (ref "C44") (pin "1") (pinfunction "1_1") (pintype "passive"))
      (node (ref "R8") (pin "2") (pinfunction "2_2") (pintype "passive"))
      (node (ref "U1") (pin "M1") (pinfunction "VREF+_M1") (pintype "power_in"))
    )
    (net (code "34") (name "/WL_REG_ON") (class "Default")
      (node (ref "U1") (pin "A9") (pinfunction "PG10_A9") (pintype "bidirectional"))
    )
    (net (code "35") (name "/W_RST") (class "Default")
      (node (ref "U1") (pin "A10") (pinfunction "PG9_A10") (pintype "bidirectional"))
    )
    (net (code "36") (name "/W_SIG") (class "Default")
      (node (ref "U1") (pin "A5") (pinfunction "PB5_A5") (pintype "bidirectional"))
    )
    (net (code "37") (name "/Y_SIG") (class "Default")
      (node (ref "U1") (pin "A4") (pinfunction "PI4_A4") (pintype "bidirectional"))
    )
    (net (code "38") (name "GND") (class "Default")
      (node (ref "C10") (pin "1") (pinfunction "1_1") (pintype "passive"))
      (node (ref "C11") (pin "1") (pinfunction "1_1") (pintype "passive"))
      (node (ref "C12") (pin "1") (pinfunction "1_1") (pintype "passive"))
      (node (ref "C13") (pin "2") (pinfunction "2_2") (pintype "passive"))
      (node (ref "C14") (pin "2") (pinfunction "2_2") (pintype "passive"))
      (node (ref "C15") (pin "2") (pinfunction "2_2") (pintype "passive"))
      (node (ref "C16") (pin "1") (pinfunction "1_1") (pintype "passive"))
      (node (ref "C17") (pin "1") (pinfunction "1_1") (pintype "passive"))
      (node (ref "C19") (pin "2") (pinfunction "2_2") (pintype "passive"))
      (node (ref "C20") (pin "2") (pinfunction "2_2") (pintype "passive"))
      (node (ref "C21") (pin "2") (pinfunction "2_2") (pintype "passive"))
      (node (ref "C22") (pin "2") (pinfunction "2_2") (pintype "passive"))
      (node (ref "C23") (pin "2") (pinfunction "2_2") (pintype "passive"))
      (node (ref "C24") (pin "2") (pinfunction "2_2") (pintype "passive"))
      (node (ref "C25") (pin "2") (pinfunction "2_2") (pintype "passive"))
      (node (ref "C26") (pin "2") (pinfunction "2_2") (pintype "passive"))
      (node (ref "C27") (pin "2") (pinfunction "2_2") (pintype "passive"))
      (node (ref "C28") (pin "2") (pinfunction "2_2") (pintype "passive"))
      (node (ref "C31") (pin "2") (pinfunction "2_2") (pintype "passive"))
      (node (ref "C32") (pin "2") (pinfunction "2_2") (pintype "passive"))
      (node (ref "C33") (pin "2") (pinfunction "2_2") (pintype "passive"))
      (node (ref "C34") (pin "2") (pinfunction "2_2") (pintype "passive"))
      (node (ref "C35") (pin "2") (pinfunction "2_2") (pintype "passive"))
      (node (ref "C36") (pin "2") (pinfunction "2_2") (pintype "passive"))
      (node (ref "C37") (pin "2") (pinfunction "2_2") (pintype "passive"))
      (node (ref "C38") (pin "2") (pinfunction "2_2") (pintype "passive"))
      (node (ref "C39") (pin "2") (pinfunction "2_2") (pintype "passive"))
      (node (ref "C40") (pin "2") (pinfunction "2_2") (pintype "passive"))
      (node (ref "C41") (pin "2") (pinfunction "2_2") (pintype "passive"))
      (node (ref "C42") (pin "2") (pinfunction "2_2") (pintype "passive"))
      (node (ref "C43") (pin "2") (pinfunction "2_2") (pintype "passive"))
      (node (ref "C44") (pin "2") (pinfunction "2_2") (pintype "passive"))
      (node (ref "C45") (pin "2") (pinfunction "2_2") (pintype "passive"))
      (node (ref "C46") (pin "2") (pinfunction "2_2") (pintype "passive"))
      (node (ref "C8") (pin "1") (pinfunction "1_1") (pintype "passive"))
      (node (ref "D10") (pin "2") (pinfunction "A_2") (pintype "passive"))
      (node (ref "D9") (pin "2") (pinfunction "A_2") (pintype "passive"))
      (node (ref "IC3") (pin "6") (pinfunction "GND_6") (pintype "passive"))
      (node (ref "IC3") (pin "7") (pinfunction "EP_7") (pintype "passive"))
      (node (ref "PS1") (pin "5") (pinfunction "-VOUT_5") (pintype "passive"))
      (node (ref "R11") (pin "1") (pinfunction "1_1") (pintype "passive"))
      (node (ref "R14") (pin "1") (pinfunction "1_1") (pintype "passive"))
      (node (ref "S1") (pin "MH1") (pinfunction "MH1_MH1") (pintype "passive"))
      (node (ref "S1") (pin "MH2") (pinfunction "MH2_MH2") (pintype "passive"))
      (node (ref "U1") (pin "A1") (pinfunction "VSS_A1") (pintype "power_in"))
      (node (ref "U1") (pin "A17") (pinfunction "VSS_A17") (pintype "power_in"))
      (node (ref "U1") (pin "A7") (pinfunction "VCAP_A7") (pintype "power_in"))
      (node (ref "U1") (pin "B2") (pinfunction "VSS_B2") (pintype "power_in"))
      (node (ref "U1") (pin "B6") (pinfunction "VSS_B6") (pintype "power_in"))
      (node (ref "U1") (pin "C10") (pinfunction "VSS_C10") (pintype "power_in"))
      (node (ref "U1") (pin "C13") (pinfunction "VSS_C13") (pintype "power_in"))
      (node (ref "U1") (pin "C16") (pinfunction "VSS_C16") (pintype "power_in"))
      (node (ref "U1") (pin "F2") (pinfunction "VSSSMPS_F2") (pintype "power_in"))
      (node (ref "U1") (pin "G10") (pinfunction "VSS_G10") (pintype "power_in"))
      (node (ref "U1") (pin "G11") (pinfunction "VSS_G11") (pintype "power_in"))
      (node (ref "U1") (pin "G16") (pinfunction "VSS_G16") (pintype "power_in"))
      (node (ref "U1") (pin "G7") (pinfunction "VSS_G7") (pintype "power_in"))
      (node (ref "U1") (pin "G8") (pinfunction "VSS_G8") (pintype "power_in"))
      (node (ref "U1") (pin "G9") (pinfunction "VSS_G9") (pintype "power_in"))
      (node (ref "U1") (pin "H10") (pinfunction "VSS_H10") (pintype "power_in"))
      (node (ref "U1") (pin "H11") (pinfunction "VSS_H11") (pintype "power_in"))
      (node (ref "U1") (pin "H7") (pinfunction "VSS_H7") (pintype "power_in"))
      (node (ref "U1") (pin "H8") (pinfunction "VSS_H8") (pintype "power_in"))
      (node (ref "U1") (pin "H9") (pinfunction "VSS_H9") (pintype "power_in"))
      (node (ref "U1") (pin "J10") (pinfunction "VSS_J10") (pintype "power_in"))
      (node (ref "U1") (pin "J11") (pinfunction "VSS_J11") (pintype "power_in"))
      (node (ref "U1") (pin "J3") (pinfunction "VSS_J3") (pintype "power_in"))
      (node (ref "U1") (pin "J7") (pinfunction "VSS_J7") (pintype "power_in"))
      (node (ref "U1") (pin "J8") (pinfunction "VSS_J8") (pintype "power_in"))
      (node (ref "U1") (pin "J9") (pinfunction "VSS_J9") (pintype "power_in"))
      (node (ref "U1") (pin "K10") (pinfunction "VSS_K10") (pintype "power_in"))
      (node (ref "U1") (pin "K11") (pinfunction "VSS_K11") (pintype "power_in"))
      (node (ref "U1") (pin "K7") (pinfunction "VSS_K7") (pintype "power_in"))
      (node (ref "U1") (pin "K8") (pinfunction "VSS_K8") (pintype "power_in"))
      (node (ref "U1") (pin "K9") (pinfunction "VSS_K9") (pintype "power_in"))
      (node (ref "U1") (pin "L10") (pinfunction "VSS_L10") (pintype "power_in"))
      (node (ref "U1") (pin "L11") (pinfunction "VSS_L11") (pintype "power_in"))
      (node (ref "U1") (pin "L7") (pinfunction "VSS_L7") (pintype "power_in"))
      (node (ref "U1") (pin "L8") (pinfunction "VSS_L8") (pintype "power_in"))
      (node (ref "U1") (pin "L9") (pinfunction "VSS_L9") (pintype "power_in"))
      (node (ref "U1") (pin "N1") (pinfunction "VREF-_N1") (pintype "power_in"))
      (node (ref "U1") (pin "N16") (pinfunction "VSS_N16") (pintype "power_in"))
      (node (ref "U1") (pin "P1") (pinfunction "VSSA_P1") (pintype "power_in"))
      (node (ref "U1") (pin "R4") (pinfunction "VSS_R4") (pintype "power_in"))
      (node (ref "U1") (pin "R8") (pinfunction "VSS_R8") (pintype "power_in"))
      (node (ref "U1") (pin "T12") (pinfunction "VSS_T12") (pintype "power_in"))
      (node (ref "U1") (pin "U1") (pinfunction "VSS_U1") (pintype "bidirectional"))
      (node (ref "U1") (pin "U17") (pinfunction "VSS_U17") (pintype "power_in"))
      (node (ref "Y1") (pin "2") (pinfunction "GND_2") (pintype "passive"))
    )
    (net (code "39") (name "Net-(C7-Pad1)") (class "Default")
      (node (ref "C7") (pin "1") (pinfunction "1_1") (pintype "passive"))
      (node (ref "C9") (pin "1") (pinfunction "1_1") (pintype "passive"))
      (node (ref "U1") (pin "J16") (pinfunction "VSSDSI_J16") (pintype "power_in"))
      (node (ref "U1") (pin "J17") (pinfunction "VSSDSI_J17") (pintype "power_in"))
      (node (ref "U1") (pin "K15") (pinfunction "VSSDSI_K15") (pintype "power_in"))
      (node (ref "U1") (pin "L15") (pinfunction "VSSDSI_L15") (pintype "power_in"))
      (node (ref "U1") (pin "M15") (pinfunction "VSSDSI_M15") (pintype "power_in"))
    )
    (net (code "40") (name "Net-(C8-Pad2)") (class "Default")
      (node (ref "C8") (pin "2") (pinfunction "2_2") (pintype "passive"))
      (node (ref "U1") (pin "U11") (pinfunction "VCAP_U11") (pintype "power_in"))
    )
    (net (code "41") (name "Net-(C10-Pad2)") (class "Default")
      (node (ref "C10") (pin "2") (pinfunction "2_2") (pintype "passive"))
      (node (ref "U1") (pin "D17") (pinfunction "VCAP_D17") (pintype "power_in"))
    )
    (net (code "42") (name "Net-(C13-Pad1)") (class "Default")
      (node (ref "C13") (pin "1") (pinfunction "1_1") (pintype "passive"))
      (node (ref "R15") (pin "2") (pinfunction "2_2") (pintype "passive"))
      (node (ref "Y2") (pin "1") (pinfunction "1_1") (pintype "passive"))
    )
    (net (code "43") (name "Net-(C14-Pad1)") (class "Default")
      (node (ref "C14") (pin "1") (pinfunction "1_1") (pintype "passive"))
      (node (ref "R16") (pin "2") (pinfunction "2_2") (pintype "passive"))
      (node (ref "Y2") (pin "2") (pinfunction "2_2") (pintype "passive"))
    )
    (net (code "44") (name "Net-(D9-C)") (class "Default")
      (node (ref "D9") (pin "1") (pinfunction "C_1") (pintype "passive"))
      (node (ref "R6") (pin "2") (pinfunction "2_2") (pintype "passive"))
    )
    (net (code "45") (name "Net-(D10-C)") (class "Default")
      (node (ref "D10") (pin "1") (pinfunction "C_1") (pintype "passive"))
      (node (ref "R10") (pin "2") (pinfunction "2_2") (pintype "passive"))
    )
    (net (code "46") (name "Net-(J7-Pad1)") (class "Default")
      (node (ref "J7") (pin "1") (pinfunction "1_1") (pintype "passive"))
      (node (ref "S1") (pin "1") (pinfunction "1_1") (pintype "passive"))
    )
    (net (code "47") (name "Net-(PS1-+VIN_(VCC))") (class "Default")
      (node (ref "C18") (pin "1") (pinfunction "1_1") (pintype "passive"))
      (node (ref "FL1") (pin "3") (pinfunction "3_3") (pintype "passive"))
      (node (ref "PS1") (pin "1") (pinfunction "+VIN_(VCC)_1") (pintype "passive"))
    )
    (net (code "48") (name "Net-(PS1--VIN_(GND))") (class "Default")
      (node (ref "C31") (pin "1") (pinfunction "1_1") (pintype "passive"))
      (node (ref "FL1") (pin "4") (pinfunction "4_4") (pintype "passive"))
      (node (ref "PS1") (pin "2") (pinfunction "-VIN_(GND)_2") (pintype "passive"))
    )
    (net (code "49") (name "Net-(U1C-PC14-OSC32_IN)") (class "Default")
      (node (ref "R16") (pin "1") (pinfunction "1_1") (pintype "passive"))
      (node (ref "U1") (pin "C2") (pinfunction "PC14-OSC32_IN_C2") (pintype "bidirectional"))
    )
    (net (code "50") (name "Net-(U1C-PC15-OSC32_OUT)") (class "Default")
      (node (ref "R15") (pin "1") (pinfunction "1_1") (pintype "passive"))
      (node (ref "U1") (pin "C1") (pinfunction "PC15-OSC32_OUT_C1") (pintype "bidirectional"))
    )
    (net (code "51") (name "Net-(U1D-PG0)") (class "Default")
      (node (ref "R10") (pin "1") (pinfunction "1_1") (pintype "passive"))
      (node (ref "U1") (pin "T8") (pinfunction "PG0_T8") (pintype "bidirectional"))
    )
    (net (code "52") (name "Net-(U1D-PH0-OSC_IN)") (class "Default")
      (node (ref "U1") (pin "J2") (pinfunction "PH0-OSC_IN_J2") (pintype "bidirectional"))
      (node (ref "Y1") (pin "3") (pinfunction "OUTPUT_3") (pintype "passive"))
    )
    (net (code "53") (name "Net-(U1E-PDR_ON)") (class "Default")
      (node (ref "R11") (pin "2") (pinfunction "2_2") (pintype "passive"))
      (node (ref "R12") (pin "2") (pinfunction "2_2") (pintype "passive"))
      (node (ref "U1") (pin "E7") (pinfunction "PDR_ON_E7") (pintype "power_in"))
    )
    (net (code "54") (name "Net-(Y1-STAND-BY)") (class "Default")
      (node (ref "R9") (pin "1") (pinfunction "1_1") (pintype "passive"))
      (node (ref "Y1") (pin "1") (pinfunction "STAND-BY_1") (pintype "passive"))
    )
    (net (code "55") (name "unconnected-(IC3-N.C._1-Pad1)") (class "Default")
      (node (ref "IC3") (pin "1") (pinfunction "N.C._1_1") (pintype "passive+no_connect"))
    )
    (net (code "56") (name "unconnected-(IC3-N.C._2-Pad4)") (class "Default")
      (node (ref "IC3") (pin "4") (pinfunction "N.C._2_4") (pintype "passive+no_connect"))
    )
    (net (code "57") (name "unconnected-(IC3-N.C._3-Pad5)") (class "Default")
      (node (ref "IC3") (pin "5") (pinfunction "N.C._3_5") (pintype "passive+no_connect"))
    )
    (net (code "58") (name "unconnected-(PS1-REMOTE_ON{slash}OFF-Pad6)") (class "Default")
      (node (ref "PS1") (pin "6") (pinfunction "REMOTE_ON/OFF_6") (pintype "passive+no_connect"))
    )
    (net (code "59") (name "unconnected-(PS1-TRIM-Pad4)") (class "Default")
      (node (ref "PS1") (pin "4") (pinfunction "TRIM_4") (pintype "passive+no_connect"))
    )
    (net (code "60") (name "unconnected-(S1-Pad3)") (class "Default")
      (node (ref "S1") (pin "3") (pinfunction "3_3") (pintype "passive+no_connect"))
    )
    (net (code "61") (name "unconnected-(U1B-VBAT-PadB1)") (class "Default")
      (node (ref "U1") (pin "B1") (pinfunction "VBAT_B1") (pintype "power_in+no_connect"))
    )
    (net (code "62") (name "unconnected-(U1B-VDD33USB-PadF17)") (class "Default")
      (node (ref "U1") (pin "F17") (pinfunction "VDD33USB_F17") (pintype "power_in+no_connect"))
    )
    (net (code "63") (name "unconnected-(U1B-VDD50USB-PadG17)") (class "Default")
      (node (ref "U1") (pin "G17") (pinfunction "VDD50USB_G17") (pintype "power_in+no_connect"))
    )
    (net (code "64") (name "unconnected-(U1B-VDDSMPS-PadF1)") (class "Default")
      (node (ref "U1") (pin "F1") (pinfunction "VDDSMPS_F1") (pintype "power_in"))
    )
    (net (code "65") (name "unconnected-(U1C-PA0-PadN5)") (class "Default")
      (node (ref "U1") (pin "N5") (pinfunction "PA0_N5") (pintype "bidirectional+no_connect"))
    )
    (net (code "66") (name "unconnected-(U1C-PA0_C-PadT1)") (class "Default")
      (node (ref "U1") (pin "T1") (pinfunction "PA0_C_T1") (pintype "bidirectional+no_connect"))
    )
    (net (code "67") (name "unconnected-(U1C-PA1-PadN4)") (class "Default")
      (node (ref "U1") (pin "N4") (pinfunction "PA1_N4") (pintype "bidirectional+no_connect"))
    )
    (net (code "68") (name "unconnected-(U1C-PA1_C-PadT2)") (class "Default")
      (node (ref "U1") (pin "T2") (pinfunction "PA1_C_T2") (pintype "bidirectional+no_connect"))
    )
    (net (code "69") (name "unconnected-(U1C-PA2-PadN3)") (class "Default")
      (node (ref "U1") (pin "N3") (pinfunction "PA2_N3") (pintype "bidirectional+no_connect"))
    )
    (net (code "70") (name "unconnected-(U1C-PA3-PadU2)") (class "Default")
      (node (ref "U1") (pin "U2") (pinfunction "PA3_U2") (pintype "bidirectional+no_connect"))
    )
    (net (code "71") (name "unconnected-(U1C-PA4-PadU3)") (class "Default")
      (node (ref "U1") (pin "U3") (pinfunction "PA4_U3") (pintype "bidirectional+no_connect"))
    )
    (net (code "72") (name "unconnected-(U1C-PA5-PadT3)") (class "Default")
      (node (ref "U1") (pin "T3") (pinfunction "PA5_T3") (pintype "bidirectional+no_connect"))
    )
    (net (code "73") (name "unconnected-(U1C-PA6-PadR3)") (class "Default")
      (node (ref "U1") (pin "R3") (pinfunction "PA6_R3") (pintype "bidirectional+no_connect"))
    )
    (net (code "74") (name "unconnected-(U1C-PA7-PadR5)") (class "Default")
      (node (ref "U1") (pin "R5") (pinfunction "PA7_R5") (pintype "bidirectional+no_connect"))
    )
    (net (code "75") (name "unconnected-(U1C-PA8-PadE15)") (class "Default")
      (node (ref "U1") (pin "E15") (pinfunction "PA8_E15") (pintype "bidirectional+no_connect"))
    )
    (net (code "76") (name "unconnected-(U1C-PA9-PadD15)") (class "Default")
      (node (ref "U1") (pin "D15") (pinfunction "PA9_D15") (pintype "bidirectional+no_connect"))
    )
    (net (code "77") (name "unconnected-(U1C-PA10-PadD14)") (class "Default")
      (node (ref "U1") (pin "D14") (pinfunction "PA10_D14") (pintype "bidirectional+no_connect"))
    )
    (net (code "78") (name "unconnected-(U1C-PA11-PadE17)") (class "Default")
      (node (ref "U1") (pin "E17") (pinfunction "PA11_E17") (pintype "bidirectional+no_connect"))
    )
    (net (code "79") (name "unconnected-(U1C-PA12-PadE16)") (class "Default")
      (node (ref "U1") (pin "E16") (pinfunction "PA12_E16") (pintype "bidirectional+no_connect"))
    )
    (net (code "80") (name "unconnected-(U1C-PB0-PadU5)") (class "Default")
      (node (ref "U1") (pin "U5") (pinfunction "PB0_U5") (pintype "bidirectional+no_connect"))
    )
    (net (code "81") (name "unconnected-(U1C-PB1-PadT5)") (class "Default")
      (node (ref "U1") (pin "T5") (pinfunction "PB1_T5") (pintype "bidirectional+no_connect"))
    )
    (net (code "82") (name "unconnected-(U1C-PB2-PadR6)") (class "Default")
      (node (ref "U1") (pin "R6") (pinfunction "PB2_R6") (pintype "bidirectional+no_connect"))
    )
    (net (code "83") (name "unconnected-(U1C-PB6-PadB5)") (class "Default")
      (node (ref "U1") (pin "B5") (pinfunction "PB6_B5") (pintype "bidirectional+no_connect"))
    )
    (net (code "84") (name "unconnected-(U1C-PB7-PadC5)") (class "Default")
      (node (ref "U1") (pin "C5") (pinfunction "PB7_C5") (pintype "bidirectional+no_connect"))
    )
    (net (code "85") (name "unconnected-(U1C-PB8-PadD5)") (class "Default")
      (node (ref "U1") (pin "D5") (pinfunction "PB8_D5") (pintype "bidirectional+no_connect"))
    )
    (net (code "86") (name "unconnected-(U1C-PB9-PadD4)") (class "Default")
      (node (ref "U1") (pin "D4") (pinfunction "PB9_D4") (pintype "bidirectional+no_connect"))
    )
    (net (code "87") (name "unconnected-(U1C-PB10-PadP11)") (class "Default")
      (node (ref "U1") (pin "P11") (pinfunction "PB10_P11") (pintype "bidirectional+no_connect"))
    )
    (net (code "88") (name "unconnected-(U1C-PB11-PadP12)") (class "Default")
      (node (ref "U1") (pin "P12") (pinfunction "PB11_P12") (pintype "bidirectional+no_connect"))
    )
    (net (code "89") (name "unconnected-(U1C-PB12-PadT14)") (class "Default")
      (node (ref "U1") (pin "T14") (pinfunction "PB12_T14") (pintype "bidirectional+no_connect"))
    )
    (net (code "90") (name "unconnected-(U1C-PB13-PadU14)") (class "Default")
      (node (ref "U1") (pin "U14") (pinfunction "PB13_U14") (pintype "bidirectional+no_connect"))
    )
    (net (code "91") (name "unconnected-(U1C-PB14-PadU15)") (class "Default")
      (node (ref "U1") (pin "U15") (pinfunction "PB14_U15") (pintype "bidirectional+no_connect"))
    )
    (net (code "92") (name "unconnected-(U1C-PB15-PadT15)") (class "Default")
      (node (ref "U1") (pin "T15") (pinfunction "PB15_T15") (pintype "bidirectional+no_connect"))
    )
    (net (code "93") (name "unconnected-(U1C-PC0-PadL2)") (class "Default")
      (node (ref "U1") (pin "L2") (pinfunction "PC0_L2") (pintype "bidirectional+no_connect"))
    )
    (net (code "94") (name "unconnected-(U1C-PC1-PadM2)") (class "Default")
      (node (ref "U1") (pin "M2") (pinfunction "PC1_M2") (pintype "bidirectional+no_connect"))
    )
    (net (code "95") (name "unconnected-(U1C-PC2-PadM3)") (class "Default")
      (node (ref "U1") (pin "M3") (pinfunction "PC2_M3") (pintype "bidirectional+no_connect"))
    )
    (net (code "96") (name "unconnected-(U1C-PC2_C-PadR1)") (class "Default")
      (node (ref "U1") (pin "R1") (pinfunction "PC2_C_R1") (pintype "bidirectional+no_connect"))
    )
    (net (code "97") (name "unconnected-(U1C-PC3-PadM4)") (class "Default")
      (node (ref "U1") (pin "M4") (pinfunction "PC3_M4") (pintype "bidirectional+no_connect"))
    )
    (net (code "98") (name "unconnected-(U1C-PC3_C-PadR2)") (class "Default")
      (node (ref "U1") (pin "R2") (pinfunction "PC3_C_R2") (pintype "bidirectional+no_connect"))
    )
    (net (code "99") (name "unconnected-(U1C-PC4-PadT4)") (class "Default")
      (node (ref "U1") (pin "T4") (pinfunction "PC4_T4") (pintype "bidirectional+no_connect"))
    )
    (net (code "100") (name "unconnected-(U1C-PC5-PadU4)") (class "Default")
      (node (ref "U1") (pin "U4") (pinfunction "PC5_U4") (pintype "bidirectional+no_connect"))
    )
    (net (code "101") (name "unconnected-(U1C-PC6-PadF14)") (class "Default")
      (node (ref "U1") (pin "F14") (pinfunction "PC6_F14") (pintype "bidirectional+no_connect"))
    )
    (net (code "102") (name "unconnected-(U1C-PC7-PadF13)") (class "Default")
      (node (ref "U1") (pin "F13") (pinfunction "PC7_F13") (pintype "bidirectional+no_connect"))
    )
    (net (code "103") (name "unconnected-(U1C-PC13-PadE3)") (class "Default")
      (node (ref "U1") (pin "E3") (pinfunction "PC13_E3") (pintype "bidirectional+no_connect"))
    )
    (net (code "104") (name "unconnected-(U1C-PD0-PadD13)") (class "Default")
      (node (ref "U1") (pin "D13") (pinfunction "PD0_D13") (pintype "bidirectional+no_connect"))
    )
    (net (code "105") (name "unconnected-(U1C-PD1-PadE12)") (class "Default")
      (node (ref "U1") (pin "E12") (pinfunction "PD1_E12") (pintype "bidirectional+no_connect"))
    )
    (net (code "106") (name "unconnected-(U1C-PD3-PadB12)") (class "Default")
      (node (ref "U1") (pin "B12") (pinfunction "PD3_B12") (pintype "bidirectional+no_connect"))
    )
    (net (code "107") (name "unconnected-(U1C-PD4-PadA12)") (class "Default")
      (node (ref "U1") (pin "A12") (pinfunction "PD4_A12") (pintype "bidirectional+no_connect"))
    )
    (net (code "108") (name "unconnected-(U1C-PD5-PadA11)") (class "Default")
      (node (ref "U1") (pin "A11") (pinfunction "PD5_A11") (pintype "bidirectional+no_connect"))
    )
    (net (code "109") (name "unconnected-(U1C-PD6-PadB11)") (class "Default")
      (node (ref "U1") (pin "B11") (pinfunction "PD6_B11") (pintype "bidirectional+no_connect"))
    )
    (net (code "110") (name "unconnected-(U1C-PD7-PadC11)") (class "Default")
      (node (ref "U1") (pin "C11") (pinfunction "PD7_C11") (pintype "bidirectional+no_connect"))
    )
    (net (code "111") (name "unconnected-(U1C-PD8-PadU16)") (class "Default")
      (node (ref "U1") (pin "U16") (pinfunction "PD8_U16") (pintype "bidirectional+no_connect"))
    )
    (net (code "112") (name "unconnected-(U1C-PD9-PadT17)") (class "Default")
      (node (ref "U1") (pin "T17") (pinfunction "PD9_T17") (pintype "bidirectional+no_connect"))
    )
    (net (code "113") (name "unconnected-(U1C-PD10-PadT16)") (class "Default")
      (node (ref "U1") (pin "T16") (pinfunction "PD10_T16") (pintype "bidirectional+no_connect"))
    )
    (net (code "114") (name "unconnected-(U1C-PD11-PadR15)") (class "Default")
      (node (ref "U1") (pin "R15") (pinfunction "PD11_R15") (pintype "bidirectional+no_connect"))
    )
    (net (code "115") (name "unconnected-(U1C-PD14-PadP16)") (class "Default")
      (node (ref "U1") (pin "P16") (pinfunction "PD14_P16") (pintype "bidirectional+no_connect"))
    )
    (net (code "116") (name "unconnected-(U1C-PD15-PadP15)") (class "Default")
      (node (ref "U1") (pin "P15") (pinfunction "PD15_P15") (pintype "bidirectional+no_connect"))
    )
    (net (code "117") (name "unconnected-(U1D-PE0-PadC4)") (class "Default")
      (node (ref "U1") (pin "C4") (pinfunction "PE0_C4") (pintype "bidirectional+no_connect"))
    )
    (net (code "118") (name "unconnected-(U1D-PE1-PadB4)") (class "Default")
      (node (ref "U1") (pin "B4") (pinfunction "PE1_B4") (pintype "bidirectional+no_connect"))
    )
    (net (code "119") (name "unconnected-(U1D-PE2-PadC3)") (class "Default")
      (node (ref "U1") (pin "C3") (pinfunction "PE2_C3") (pintype "bidirectional+no_connect"))
    )
    (net (code "120") (name "unconnected-(U1D-PE3-PadD3)") (class "Default")
      (node (ref "U1") (pin "D3") (pinfunction "PE3_D3") (pintype "bidirectional+no_connect"))
    )
    (net (code "121") (name "unconnected-(U1D-PE4-PadD2)") (class "Default")
      (node (ref "U1") (pin "D2") (pinfunction "PE4_D2") (pintype "bidirectional+no_connect"))
    )
    (net (code "122") (name "unconnected-(U1D-PE5-PadD1)") (class "Default")
      (node (ref "U1") (pin "D1") (pinfunction "PE5_D1") (pintype "bidirectional+no_connect"))
    )
    (net (code "123") (name "unconnected-(U1D-PE6-PadE5)") (class "Default")
      (node (ref "U1") (pin "E5") (pinfunction "PE6_E5") (pintype "bidirectional+no_connect"))
    )
    (net (code "124") (name "unconnected-(U1D-PE7-PadU9)") (class "Default")
      (node (ref "U1") (pin "U9") (pinfunction "PE7_U9") (pintype "bidirectional+no_connect"))
    )
    (net (code "125") (name "unconnected-(U1D-PE8-PadT9)") (class "Default")
      (node (ref "U1") (pin "T9") (pinfunction "PE8_T9") (pintype "bidirectional+no_connect"))
    )
    (net (code "126") (name "unconnected-(U1D-PE9-PadP9)") (class "Default")
      (node (ref "U1") (pin "P9") (pinfunction "PE9_P9") (pintype "bidirectional+no_connect"))
    )
    (net (code "127") (name "unconnected-(U1D-PE10-PadN9)") (class "Default")
      (node (ref "U1") (pin "N9") (pinfunction "PE10_N9") (pintype "bidirectional+no_connect"))
    )
    (net (code "128") (name "unconnected-(U1D-PE11-PadP10)") (class "Default")
      (node (ref "U1") (pin "P10") (pinfunction "PE11_P10") (pintype "bidirectional+no_connect"))
    )
    (net (code "129") (name "unconnected-(U1D-PE12-PadR10)") (class "Default")
      (node (ref "U1") (pin "R10") (pinfunction "PE12_R10") (pintype "bidirectional+no_connect"))
    )
    (net (code "130") (name "unconnected-(U1D-PE13-PadT10)") (class "Default")
      (node (ref "U1") (pin "T10") (pinfunction "PE13_T10") (pintype "bidirectional+no_connect"))
    )
    (net (code "131") (name "unconnected-(U1D-PE14-PadU10)") (class "Default")
      (node (ref "U1") (pin "U10") (pinfunction "PE14_U10") (pintype "bidirectional+no_connect"))
    )
    (net (code "132") (name "unconnected-(U1D-PE15-PadR11)") (class "Default")
      (node (ref "U1") (pin "R11") (pinfunction "PE15_R11") (pintype "bidirectional+no_connect"))
    )
    (net (code "133") (name "unconnected-(U1D-PF0-PadG4)") (class "Default")
      (node (ref "U1") (pin "G4") (pinfunction "PF0_G4") (pintype "bidirectional+no_connect"))
    )
    (net (code "134") (name "unconnected-(U1D-PF1-PadG3)") (class "Default")
      (node (ref "U1") (pin "G3") (pinfunction "PF1_G3") (pintype "bidirectional+no_connect"))
    )
    (net (code "135") (name "unconnected-(U1D-PF2-PadG1)") (class "Default")
      (node (ref "U1") (pin "G1") (pinfunction "PF2_G1") (pintype "bidirectional+no_connect"))
    )
    (net (code "136") (name "unconnected-(U1D-PF3-PadH4)") (class "Default")
      (node (ref "U1") (pin "H4") (pinfunction "PF3_H4") (pintype "bidirectional+no_connect"))
    )
    (net (code "137") (name "unconnected-(U1D-PF4-PadJ5)") (class "Default")
      (node (ref "U1") (pin "J5") (pinfunction "PF4_J5") (pintype "bidirectional+no_connect"))
    )
    (net (code "138") (name "unconnected-(U1D-PF5-PadJ4)") (class "Default")
      (node (ref "U1") (pin "J4") (pinfunction "PF5_J4") (pintype "bidirectional+no_connect"))
    )
    (net (code "139") (name "unconnected-(U1D-PF6-PadK2)") (class "Default")
      (node (ref "U1") (pin "K2") (pinfunction "PF6_K2") (pintype "bidirectional+no_connect"))
    )
    (net (code "140") (name "unconnected-(U1D-PF7-PadK3)") (class "Default")
      (node (ref "U1") (pin "K3") (pinfunction "PF7_K3") (pintype "bidirectional+no_connect"))
    )
    (net (code "141") (name "unconnected-(U1D-PF8-PadK4)") (class "Default")
      (node (ref "U1") (pin "K4") (pinfunction "PF8_K4") (pintype "bidirectional+no_connect"))
    )
    (net (code "142") (name "unconnected-(U1D-PF9-PadL4)") (class "Default")
      (node (ref "U1") (pin "L4") (pinfunction "PF9_L4") (pintype "bidirectional+no_connect"))
    )
    (net (code "143") (name "unconnected-(U1D-PF10-PadL3)") (class "Default")
      (node (ref "U1") (pin "L3") (pinfunction "PF10_L3") (pintype "bidirectional+no_connect"))
    )
    (net (code "144") (name "unconnected-(U1D-PF11-PadT7)") (class "Default")
      (node (ref "U1") (pin "T7") (pinfunction "PF11_T7") (pintype "bidirectional+no_connect"))
    )
    (net (code "145") (name "unconnected-(U1D-PF12-PadR7)") (class "Default")
      (node (ref "U1") (pin "R7") (pinfunction "PF12_R7") (pintype "bidirectional+no_connect"))
    )
    (net (code "146") (name "unconnected-(U1D-PF13-PadP7)") (class "Default")
      (node (ref "U1") (pin "P7") (pinfunction "PF13_P7") (pintype "bidirectional+no_connect"))
    )
    (net (code "147") (name "unconnected-(U1D-PF14-PadP8)") (class "Default")
      (node (ref "U1") (pin "P8") (pinfunction "PF14_P8") (pintype "bidirectional+no_connect"))
    )
    (net (code "148") (name "unconnected-(U1D-PF15-PadR9)") (class "Default")
      (node (ref "U1") (pin "R9") (pinfunction "PF15_R9") (pintype "bidirectional+no_connect"))
    )
    (net (code "149") (name "unconnected-(U1D-PG1-PadU8)") (class "Default")
      (node (ref "U1") (pin "U8") (pinfunction "PG1_U8") (pintype "bidirectional+no_connect"))
    )
    (net (code "150") (name "unconnected-(U1D-PG2-PadH16)") (class "Default")
      (node (ref "U1") (pin "H16") (pinfunction "PG2_H16") (pintype "bidirectional+no_connect"))
    )
    (net (code "151") (name "unconnected-(U1D-PG3-PadH15)") (class "Default")
      (node (ref "U1") (pin "H15") (pinfunction "PG3_H15") (pintype "bidirectional+no_connect"))
    )
    (net (code "152") (name "unconnected-(U1D-PG4-PadH14)") (class "Default")
      (node (ref "U1") (pin "H14") (pinfunction "PG4_H14") (pintype "bidirectional+no_connect"))
    )
    (net (code "153") (name "unconnected-(U1D-PG5-PadG14)") (class "Default")
      (node (ref "U1") (pin "G14") (pinfunction "PG5_G14") (pintype "bidirectional+no_connect"))
    )
    (net (code "154") (name "unconnected-(U1D-PG6-PadG15)") (class "Default")
      (node (ref "U1") (pin "G15") (pinfunction "PG6_G15") (pintype "bidirectional+no_connect"))
    )
    (net (code "155") (name "unconnected-(U1D-PG7-PadF16)") (class "Default")
      (node (ref "U1") (pin "F16") (pinfunction "PG7_F16") (pintype "bidirectional+no_connect"))
    )
    (net (code "156") (name "unconnected-(U1D-PG8-PadF15)") (class "Default")
      (node (ref "U1") (pin "F15") (pinfunction "PG8_F15") (pintype "bidirectional+no_connect"))
    )
    (net (code "157") (name "unconnected-(U1D-PG11-PadB9)") (class "Default")
      (node (ref "U1") (pin "B9") (pinfunction "PG11_B9") (pintype "bidirectional+no_connect"))
    )
    (net (code "158") (name "unconnected-(U1D-PG12-PadC9)") (class "Default")
      (node (ref "U1") (pin "C9") (pinfunction "PG12_C9") (pintype "bidirectional+no_connect"))
    )
    (net (code "159") (name "unconnected-(U1D-PG13-PadD9)") (class "Default")
      (node (ref "U1") (pin "D9") (pinfunction "PG13_D9") (pintype "bidirectional+no_connect"))
    )
    (net (code "160") (name "unconnected-(U1D-PG14-PadD8)") (class "Default")
      (node (ref "U1") (pin "D8") (pinfunction "PG14_D8") (pintype "bidirectional+no_connect"))
    )
    (net (code "161") (name "unconnected-(U1D-PG15-PadD6)") (class "Default")
      (node (ref "U1") (pin "D6") (pinfunction "PG15_D6") (pintype "bidirectional+no_connect"))
    )
    (net (code "162") (name "unconnected-(U1D-PH1-OSC_OUT-PadJ1)") (class "Default")
      (node (ref "U1") (pin "J1") (pinfunction "PH1-OSC_OUT_J1") (pintype "bidirectional+no_connect"))
    )
    (net (code "163") (name "unconnected-(U1D-PH2-PadN2)") (class "Default")
      (node (ref "U1") (pin "N2") (pinfunction "PH2_N2") (pintype "bidirectional+no_connect"))
    )
    (net (code "164") (name "unconnected-(U1D-PH3-PadP2)") (class "Default")
      (node (ref "U1") (pin "P2") (pinfunction "PH3_P2") (pintype "bidirectional+no_connect"))
    )
    (net (code "165") (name "unconnected-(U1D-PH4-PadP3)") (class "Default")
      (node (ref "U1") (pin "P3") (pinfunction "PH4_P3") (pintype "bidirectional+no_connect"))
    )
    (net (code "166") (name "unconnected-(U1D-PH5-PadP4)") (class "Default")
      (node (ref "U1") (pin "P4") (pinfunction "PH5_P4") (pintype "bidirectional+no_connect"))
    )
    (net (code "167") (name "unconnected-(U1D-PH6-PadT11)") (class "Default")
      (node (ref "U1") (pin "T11") (pinfunction "PH6_T11") (pintype "bidirectional+no_connect"))
    )
    (net (code "168") (name "unconnected-(U1D-PH7-PadU13)") (class "Default")
      (node (ref "U1") (pin "U13") (pinfunction "PH7_U13") (pintype "bidirectional+no_connect"))
    )
    (net (code "169") (name "unconnected-(U1D-PH8-PadT13)") (class "Default")
      (node (ref "U1") (pin "T13") (pinfunction "PH8_T13") (pintype "bidirectional+no_connect"))
    )
    (net (code "170") (name "unconnected-(U1D-PH9-PadR13)") (class "Default")
      (node (ref "U1") (pin "R13") (pinfunction "PH9_R13") (pintype "bidirectional+no_connect"))
    )
    (net (code "171") (name "unconnected-(U1D-PH10-PadP13)") (class "Default")
      (node (ref "U1") (pin "P13") (pinfunction "PH10_P13") (pintype "bidirectional+no_connect"))
    )
    (net (code "172") (name "unconnected-(U1D-PH11-PadP14)") (class "Default")
      (node (ref "U1") (pin "P14") (pinfunction "PH11_P14") (pintype "bidirectional+no_connect"))
    )
    (net (code "173") (name "unconnected-(U1D-PH12-PadR14)") (class "Default")
      (node (ref "U1") (pin "R14") (pinfunction "PH12_R14") (pintype "bidirectional+no_connect"))
    )
    (net (code "174") (name "unconnected-(U1D-PH13-PadD16)") (class "Default")
      (node (ref "U1") (pin "D16") (pinfunction "PH13_D16") (pintype "bidirectional+no_connect"))
    )
    (net (code "175") (name "unconnected-(U1D-PH14-PadB17)") (class "Default")
      (node (ref "U1") (pin "B17") (pinfunction "PH14_B17") (pintype "bidirectional+no_connect"))
    )
    (net (code "176") (name "unconnected-(U1D-PH15-PadB16)") (class "Default")
      (node (ref "U1") (pin "B16") (pinfunction "PH15_B16") (pintype "bidirectional+no_connect"))
    )
    (net (code "177") (name "unconnected-(U1E-PI0-PadA16)") (class "Default")
      (node (ref "U1") (pin "A16") (pinfunction "PI0_A16") (pintype "bidirectional+no_connect"))
    )
    (net (code "178") (name "unconnected-(U1E-PI1-PadA15)") (class "Default")
      (node (ref "U1") (pin "A15") (pinfunction "PI1_A15") (pintype "bidirectional+no_connect"))
    )
    (net (code "179") (name "unconnected-(U1E-PI2-PadB15)") (class "Default")
      (node (ref "U1") (pin "B15") (pinfunction "PI2_B15") (pintype "bidirectional+no_connect"))
    )
    (net (code "180") (name "unconnected-(U1E-PI3-PadC14)") (class "Default")
      (node (ref "U1") (pin "C14") (pinfunction "PI3_C14") (pintype "bidirectional+no_connect"))
    )
    (net (code "181") (name "unconnected-(U1E-PI7-PadB3)") (class "Default")
      (node (ref "U1") (pin "B3") (pinfunction "PI7_B3") (pintype "bidirectional+no_connect"))
    )
    (net (code "182") (name "unconnected-(U1E-PI8-PadE4)") (class "Default")
      (node (ref "U1") (pin "E4") (pinfunction "PI8_E4") (pintype "bidirectional+no_connect"))
    )
    (net (code "183") (name "unconnected-(U1E-PI9-PadE2)") (class "Default")
      (node (ref "U1") (pin "E2") (pinfunction "PI9_E2") (pintype "bidirectional+no_connect"))
    )
    (net (code "184") (name "unconnected-(U1E-PI10-PadF3)") (class "Default")
      (node (ref "U1") (pin "F3") (pinfunction "PI10_F3") (pintype "bidirectional+no_connect"))
    )
    (net (code "185") (name "unconnected-(U1E-PI11-PadF4)") (class "Default")
      (node (ref "U1") (pin "F4") (pinfunction "PI11_F4") (pintype "bidirectional+no_connect"))
    )
    (net (code "186") (name "unconnected-(U1E-PI12-PadH1)") (class "Default")
      (node (ref "U1") (pin "H1") (pinfunction "PI12_H1") (pintype "bidirectional+no_connect"))
    )
    (net (code "187") (name "unconnected-(U1E-PI13-PadH2)") (class "Default")
      (node (ref "U1") (pin "H2") (pinfunction "PI13_H2") (pintype "bidirectional+no_connect"))
    )
    (net (code "188") (name "unconnected-(U1E-PI14-PadH3)") (class "Default")
      (node (ref "U1") (pin "H3") (pinfunction "PI14_H3") (pintype "bidirectional+no_connect"))
    )
    (net (code "189") (name "unconnected-(U1E-PI15-PadP5)") (class "Default")
      (node (ref "U1") (pin "P5") (pinfunction "PI15_P5") (pintype "bidirectional+no_connect"))
    )
    (net (code "190") (name "unconnected-(U1E-PJ0-PadN6)") (class "Default")
      (node (ref "U1") (pin "N6") (pinfunction "PJ0_N6") (pintype "bidirectional+no_connect"))
    )
    (net (code "191") (name "unconnected-(U1E-PJ1-PadP6)") (class "Default")
      (node (ref "U1") (pin "P6") (pinfunction "PJ1_P6") (pintype "bidirectional+no_connect"))
    )
    (net (code "192") (name "unconnected-(U1E-PJ2-PadT6)") (class "Default")
      (node (ref "U1") (pin "T6") (pinfunction "PJ2_T6") (pintype "bidirectional+no_connect"))
    )
    (net (code "193") (name "unconnected-(U1E-PJ3-PadU6)") (class "Default")
      (node (ref "U1") (pin "U6") (pinfunction "PJ3_U6") (pintype "bidirectional+no_connect"))
    )
    (net (code "194") (name "unconnected-(U1E-PJ4-PadU7)") (class "Default")
      (node (ref "U1") (pin "U7") (pinfunction "PJ4_U7") (pintype "bidirectional+no_connect"))
    )
    (net (code "195") (name "unconnected-(U1E-PJ5-PadR12)") (class "Default")
      (node (ref "U1") (pin "R12") (pinfunction "PJ5_R12") (pintype "bidirectional+no_connect"))
    )
    (net (code "196") (name "unconnected-(U1E-PJ6-PadN15)") (class "Default")
      (node (ref "U1") (pin "N15") (pinfunction "PJ6_N15") (pintype "bidirectional+no_connect"))
    )
    (net (code "197") (name "unconnected-(U1E-PJ7-PadN14)") (class "Default")
      (node (ref "U1") (pin "N14") (pinfunction "PJ7_N14") (pintype "bidirectional+no_connect"))
    )
    (net (code "198") (name "unconnected-(U1E-PJ8-PadN13)") (class "Default")
      (node (ref "U1") (pin "N13") (pinfunction "PJ8_N13") (pintype "bidirectional+no_connect"))
    )
    (net (code "199") (name "unconnected-(U1E-PJ9-PadM14)") (class "Default")
      (node (ref "U1") (pin "M14") (pinfunction "PJ9_M14") (pintype "bidirectional+no_connect"))
    )
    (net (code "200") (name "unconnected-(U1E-PJ10-PadL14)") (class "Default")
      (node (ref "U1") (pin "L14") (pinfunction "PJ10_L14") (pintype "bidirectional+no_connect"))
    )
    (net (code "201") (name "unconnected-(U1E-PJ11-PadK14)") (class "Default")
      (node (ref "U1") (pin "K14") (pinfunction "PJ11_K14") (pintype "bidirectional+no_connect"))
    )
    (net (code "202") (name "unconnected-(U1E-PJ12-PadD11)") (class "Default")
      (node (ref "U1") (pin "D11") (pinfunction "PJ12_D11") (pintype "bidirectional+no_connect"))
    )
    (net (code "203") (name "unconnected-(U1E-PJ13-PadE10)") (class "Default")
      (node (ref "U1") (pin "E10") (pinfunction "PJ13_E10") (pintype "bidirectional+no_connect"))
    )
    (net (code "204") (name "unconnected-(U1E-PJ14-PadD10)") (class "Default")
      (node (ref "U1") (pin "D10") (pinfunction "PJ14_D10") (pintype "bidirectional+no_connect"))
    )
    (net (code "205") (name "unconnected-(U1E-PJ15-PadB10)") (class "Default")
      (node (ref "U1") (pin "B10") (pinfunction "PJ15_B10") (pintype "bidirectional+no_connect"))
    )
    (net (code "206") (name "unconnected-(U1E-PK0-PadJ14)") (class "Default")
      (node (ref "U1") (pin "J14") (pinfunction "PK0_J14") (pintype "bidirectional+no_connect"))
    )
    (net (code "207") (name "unconnected-(U1E-PK1-PadJ15)") (class "Default")
      (node (ref "U1") (pin "J15") (pinfunction "PK1_J15") (pintype "passive+no_connect"))
    )
    (net (code "208") (name "unconnected-(U1E-PK2-PadH17)") (class "Default")
      (node (ref "U1") (pin "H17") (pinfunction "PK2_H17") (pintype "bidirectional+no_connect"))
    )
    (net (code "209") (name "unconnected-(U1E-PK3-PadC8)") (class "Default")
      (node (ref "U1") (pin "C8") (pinfunction "PK3_C8") (pintype "bidirectional+no_connect"))
    )
    (net (code "210") (name "unconnected-(U1E-PK4-PadB8)") (class "Default")
      (node (ref "U1") (pin "B8") (pinfunction "PK4_B8") (pintype "bidirectional+no_connect"))
    )
    (net (code "211") (name "unconnected-(U1E-PK5-PadA8)") (class "Default")
      (node (ref "U1") (pin "A8") (pinfunction "PK5_A8") (pintype "bidirectional+no_connect"))
    )
    (net (code "212") (name "unconnected-(U1E-PK6-PadC7)") (class "Default")
      (node (ref "U1") (pin "C7") (pinfunction "PK6_C7") (pintype "bidirectional+no_connect"))
    )
    (net (code "213") (name "unconnected-(U1E-PK7-PadD7)") (class "Default")
      (node (ref "U1") (pin "D7") (pinfunction "PK7_D7") (pintype "bidirectional+no_connect"))
    )
    (net (code "214") (name "unconnected-(U1E-VFBSMPS-PadG2)") (class "Default")
      (node (ref "U1") (pin "G2") (pinfunction "VFBSMPS_G2") (pintype "power_in+no_connect"))
    )
    (net (code "215") (name "unconnected-(U1E-VLXSMPS-PadE1)") (class "Default")
      (node (ref "U1") (pin "E1") (pinfunction "VLXSMPS_E1") (pintype "power_in+no_connect"))
    )
  )
)
